# UVandLight_I2C_V2.net
KiCad netlist of a schematic drawn in EAGLE
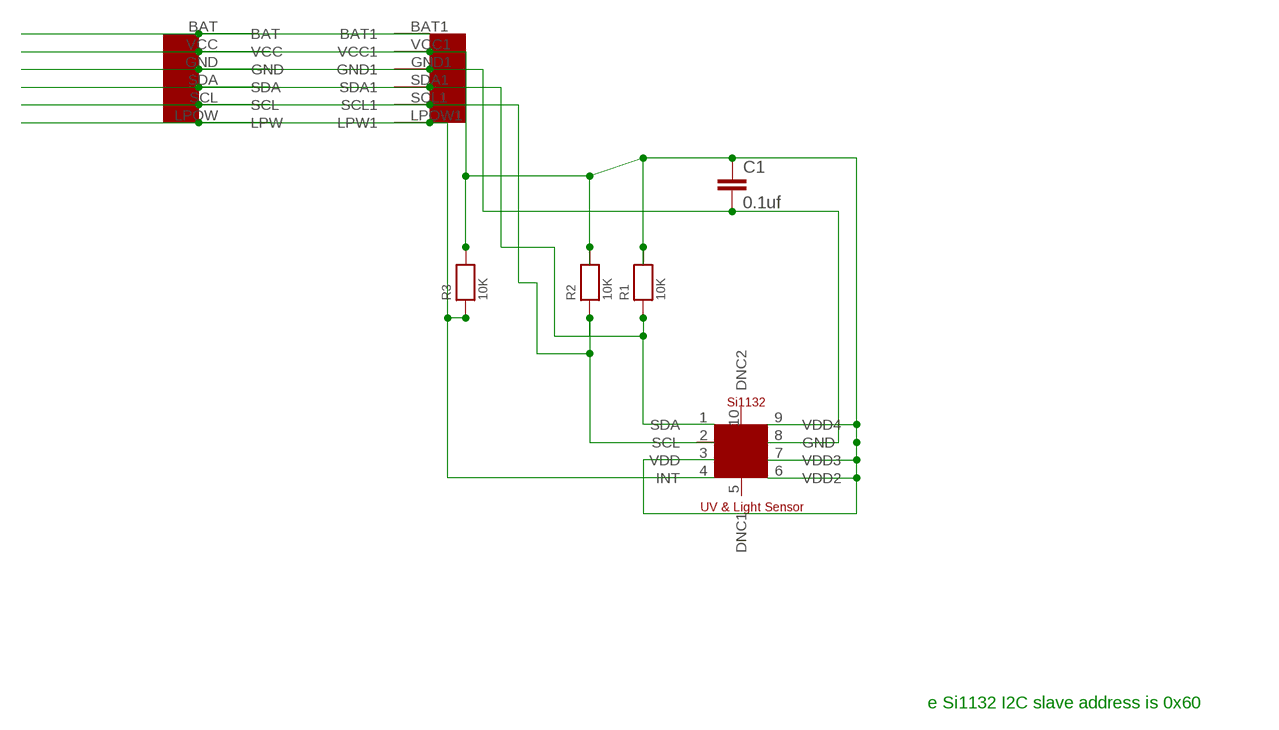
[diagram p0: schematic, sheet 1]

(export (version "E")
  (design (tool "Eeschema 10.0.6"))
  (components
    (comp (ref "C1")
      (value "0.1uf")
      (footprint "eagle-import:0402-CAP")
      (libsource (lib "eagle-import") (part "CAP0402-CAP"))
    )
    (comp (ref "R1")
      (value "10K")
      (footprint "eagle-import:0402")
      (libsource (lib "eagle-import") (part "RESISTOR0402"))
    )
    (comp (ref "R2")
      (value "10K")
      (footprint "eagle-import:0402")
      (libsource (lib "eagle-import") (part "RESISTOR0402"))
    )
    (comp (ref "R3")
      (value "10K")
      (footprint "eagle-import:0402")
      (libsource (lib "eagle-import") (part "RESISTOR0402"))
    )
    (comp (ref "U$1")
      (value "EZ-I2CHEADERV1")
      (footprint "eagle-import:EZ-I2CHEADERV1")
      (libsource (lib "eagle-import") (part "EZ-I2CHEADERV1"))
    )
    (comp (ref "U$2")
      (value "UV-SI1132")
      (footprint "eagle-import:UV-SI1132")
      (libsource (lib "eagle-import") (part "UV-SI1132"))
    )
  )
  (nets
    (net (code "1") (name "Net-(U$1-LPW)") (class "Default")
      (node (ref "R3") (pin "1") (pinfunction "1_1") (pintype "passive"))
      (node (ref "U$1") (pin "LPOW") (pinfunction "LPW_LPOW") (pintype "bidirectional"))
      (node (ref "U$1") (pin "LPOW1") (pinfunction "LPW1_LPOW1") (pintype "bidirectional"))
      (node (ref "U$2") (pin "4") (pinfunction "INT_4") (pintype "bidirectional"))
    )
    (net (code "2") (name "Net-(U$1-PadBAT)") (class "Default")
      (node (ref "U$1") (pin "BAT") (pinfunction "BAT_BAT") (pintype "bidirectional"))
      (node (ref "U$1") (pin "BAT1") (pinfunction "BAT1_BAT1") (pintype "bidirectional"))
    )
    (net (code "3") (name "Net-(U$2-GND)") (class "Default")
      (node (ref "C1") (pin "2") (pinfunction "2_2") (pintype "passive"))
      (node (ref "U$1") (pin "GND") (pinfunction "GND_GND") (pintype "bidirectional"))
      (node (ref "U$1") (pin "GND1") (pinfunction "GND1_GND1") (pintype "bidirectional"))
      (node (ref "U$2") (pin "8") (pinfunction "GND_8") (pintype "bidirectional"))
    )
    (net (code "4") (name "Net-(U$2-SCL)") (class "Default")
      (node (ref "R2") (pin "1") (pinfunction "1_1") (pintype "passive"))
      (node (ref "U$1") (pin "SCL") (pinfunction "SCL_SCL") (pintype "bidirectional"))
      (node (ref "U$1") (pin "SCL1") (pinfunction "SCL1_SCL1") (pintype "bidirectional"))
      (node (ref "U$2") (pin "2") (pinfunction "SCL_2") (pintype "bidirectional"))
    )
    (net (code "5") (name "Net-(U$2-SDA)") (class "Default")
      (node (ref "R1") (pin "1") (pinfunction "1_1") (pintype "passive"))
      (node (ref "U$1") (pin "SDA") (pinfunction "SDA_SDA") (pintype "bidirectional"))
      (node (ref "U$1") (pin "SDA1") (pinfunction "SDA1_SDA1") (pintype "bidirectional"))
      (node (ref "U$2") (pin "1") (pinfunction "SDA_1") (pintype "bidirectional"))
    )
    (net (code "6") (name "Net-(U$2-VDD)") (class "Default")
      (node (ref "C1") (pin "1") (pinfunction "1_1") (pintype "passive"))
      (node (ref "R1") (pin "2") (pinfunction "2_2") (pintype "passive"))
      (node (ref "R2") (pin "2") (pinfunction "2_2") (pintype "passive"))
      (node (ref "R3") (pin "2") (pinfunction "2_2") (pintype "passive"))
      (node (ref "U$1") (pin "VCC") (pinfunction "VCC_VCC") (pintype "bidirectional"))
      (node (ref "U$1") (pin "VCC1") (pinfunction "VCC1_VCC1") (pintype "bidirectional"))
      (node (ref "U$2") (pin "3") (pinfunction "VDD_3") (pintype "bidirectional"))
      (node (ref "U$2") (pin "6") (pinfunction "VDD2_6") (pintype "bidirectional"))
      (node (ref "U$2") (pin "7") (pinfunction "VDD3_7") (pintype "bidirectional"))
      (node (ref "U$2") (pin "9") (pinfunction "VDD4_9") (pintype "bidirectional"))
    )
    (net (code "7") (name "unconnected-(U$2-DNC1-Pad5)") (class "Default")
      (node (ref "U$2") (pin "5") (pinfunction "DNC1_5") (pintype "bidirectional"))
    )
    (net (code "8") (name "unconnected-(U$2-DNC2-Pad10)") (class "Default")
      (node (ref "U$2") (pin "10") (pinfunction "DNC2_10") (pintype "bidirectional"))
    )
  )
)
